# PortBreakoutCapacitive_r3_no_user.net
KiCad netlist of a schematic drawn in EAGLE
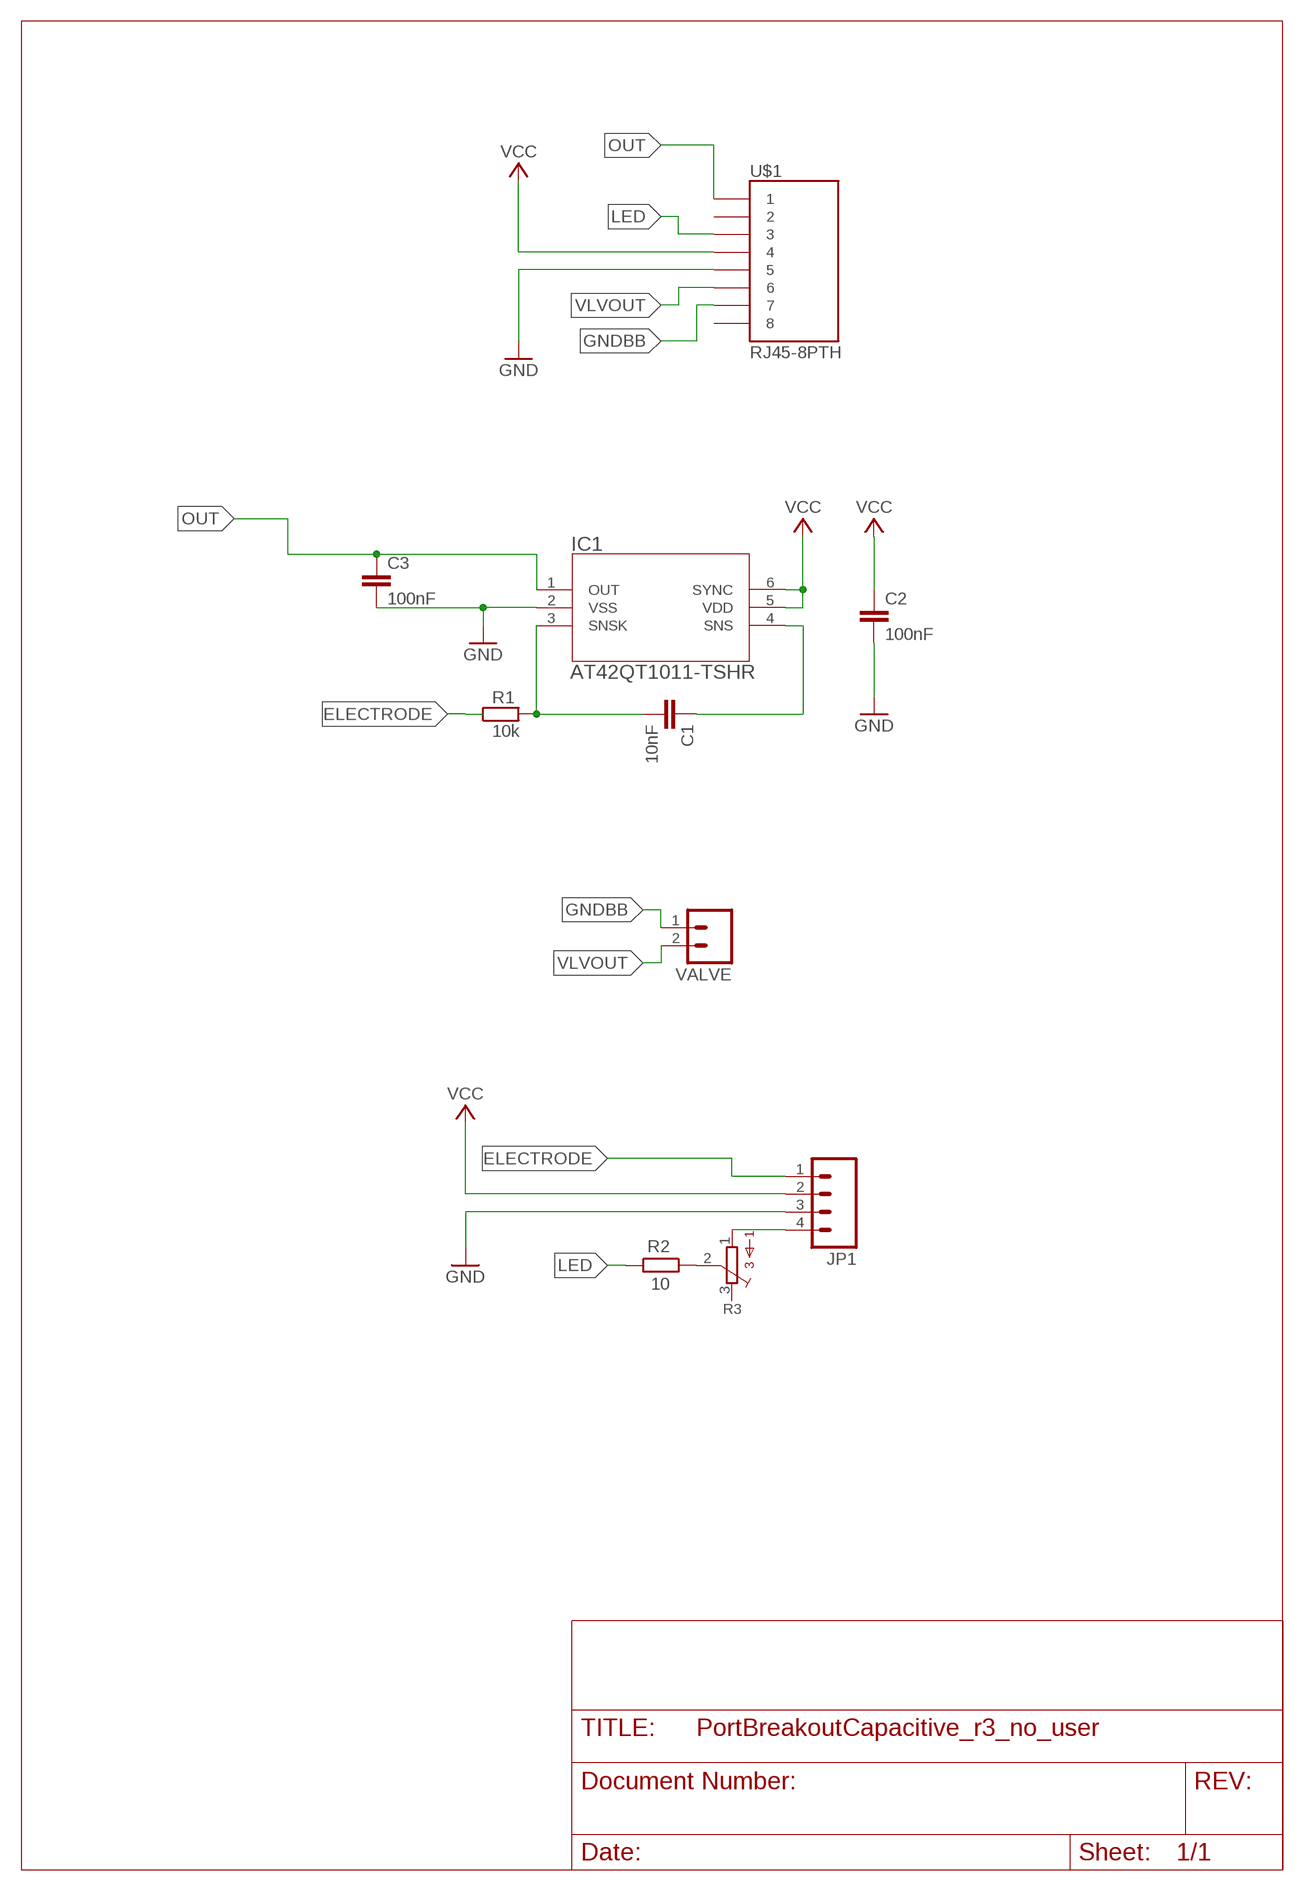
[diagram p0: schematic, sheet 1]

(export (version "E")
  (design (tool "Eeschema 10.0.6"))
  (components
    (comp (ref "C1")
      (value "10nF")
      (footprint "eagle-import:C1206")
      (libsource (lib "eagle-import") (part "C-EUC1206"))
    )
    (comp (ref "C2")
      (value "100nF")
      (footprint "eagle-import:C1206")
      (libsource (lib "eagle-import") (part "C-EUC1206"))
    )
    (comp (ref "C3")
      (value "100nF")
      (footprint "eagle-import:C1206")
      (libsource (lib "eagle-import") (part "C-EUC1206"))
    )
    (comp (ref "IC1")
      (value "AT42QT1011-TSHR")
      (footprint "eagle-import:6ST1_ATM")
      (fields (field (name "MANUFACTURER_PART_NUMBER") "AT42QT1010-TSHR"))
      (libsource (lib "eagle-import") (part "AT42QT1010-TSHR"))
    )
    (comp (ref "JP1")
      (value "CONN_04SCREW")
      (footprint "eagle-import:SCREWTERMINAL-3.5MM-4")
      (libsource (lib "eagle-import") (part "CONN_04SCREW"))
    )
    (comp (ref "R1")
      (value "10k")
      (footprint "eagle-import:R1206")
      (libsource (lib "eagle-import") (part "R-EU_R1206"))
    )
    (comp (ref "R2")
      (value "10")
      (footprint "eagle-import:R1206")
      (libsource (lib "eagle-import") (part "R-EU_R1206"))
    )
    (comp (ref "R3")
      (value "3362R")
      (footprint "eagle-import:3362R")
      (libsource (lib "eagle-import") (part "3362R"))
    )
    (comp (ref "U$1")
      (value "RJ45-8PTH")
      (footprint "eagle-import:RJ45-8")
      (libsource (lib "eagle-import") (part "RJ45-8PTH"))
    )
    (comp (ref "VALVE")
      (value "M023.5MM_LOCK")
      (footprint "eagle-import:SCREWTERMINAL-3.5MM-2_LOCK")
      (libsource (lib "eagle-import") (part "M023.5MM_LOCK"))
    )
  )
  (nets
    (net (code "1") (name "ELECTRODE") (class "Default")
      (node (ref "JP1") (pin "1") (pinfunction "1_1") (pintype "passive"))
      (node (ref "R1") (pin "1") (pinfunction "1_1") (pintype "passive"))
    )
    (net (code "2") (name "GND") (class "Default")
      (node (ref "C2") (pin "2") (pinfunction "2_2") (pintype "passive"))
      (node (ref "C3") (pin "2") (pinfunction "2_2") (pintype "passive"))
      (node (ref "IC1") (pin "2") (pinfunction "VSS_2") (pintype "power_in"))
      (node (ref "JP1") (pin "3") (pinfunction "3_3") (pintype "passive"))
      (node (ref "U$1") (pin "5") (pinfunction "5_5") (pintype "bidirectional"))
    )
    (net (code "3") (name "GNDBB") (class "Default")
      (node (ref "U$1") (pin "7") (pinfunction "7_7") (pintype "bidirectional"))
      (node (ref "VALVE") (pin "1") (pinfunction "1_1") (pintype "passive"))
    )
    (net (code "4") (name "LED") (class "Default")
      (node (ref "R2") (pin "2") (pinfunction "2_2") (pintype "passive"))
      (node (ref "U$1") (pin "3") (pinfunction "3_3") (pintype "bidirectional"))
    )
    (net (code "5") (name "Net-(IC1-SNS)") (class "Default")
      (node (ref "C1") (pin "1") (pinfunction "1_1") (pintype "passive"))
      (node (ref "IC1") (pin "4") (pinfunction "SNS_4") (pintype "bidirectional"))
    )
    (net (code "6") (name "Net-(IC1-SNSK)") (class "Default")
      (node (ref "C1") (pin "2") (pinfunction "2_2") (pintype "passive"))
      (node (ref "IC1") (pin "3") (pinfunction "SNSK_3") (pintype "bidirectional"))
      (node (ref "R1") (pin "2") (pinfunction "2_2") (pintype "passive"))
    )
    (net (code "7") (name "Net-(JP1-Pad4)") (class "Default")
      (node (ref "JP1") (pin "4") (pinfunction "4_4") (pintype "passive"))
      (node (ref "R3") (pin "1") (pinfunction "1_1") (pintype "passive"))
    )
    (net (code "8") (name "Net-(R2-Pad1)") (class "Default")
      (node (ref "R2") (pin "1") (pinfunction "1_1") (pintype "passive"))
      (node (ref "R3") (pin "2") (pinfunction "2_2") (pintype "passive"))
    )
    (net (code "9") (name "OUT") (class "Default")
      (node (ref "C3") (pin "1") (pinfunction "1_1") (pintype "passive"))
      (node (ref "IC1") (pin "1") (pinfunction "OUT_1") (pintype "output"))
      (node (ref "U$1") (pin "1") (pinfunction "1_1") (pintype "bidirectional"))
    )
    (net (code "10") (name "VCC") (class "Default")
      (node (ref "C2") (pin "1") (pinfunction "1_1") (pintype "passive"))
      (node (ref "IC1") (pin "5") (pinfunction "VDD_5") (pintype "power_in"))
      (node (ref "IC1") (pin "6") (pinfunction "SYNC_6") (pintype "input"))
      (node (ref "JP1") (pin "2") (pinfunction "2_2") (pintype "passive"))
      (node (ref "U$1") (pin "4") (pinfunction "4_4") (pintype "bidirectional"))
    )
    (net (code "11") (name "VLVOUT") (class "Default")
      (node (ref "U$1") (pin "6") (pinfunction "6_6") (pintype "bidirectional"))
      (node (ref "VALVE") (pin "2") (pinfunction "2_2") (pintype "passive"))
    )
    (net (code "12") (name "unconnected-(R3-Pad3)") (class "Default")
      (node (ref "R3") (pin "3") (pinfunction "3_3") (pintype "passive"))
    )
    (net (code "13") (name "unconnected-(U$1-Pad2)") (class "Default")
      (node (ref "U$1") (pin "2") (pinfunction "2_2") (pintype "bidirectional"))
    )
    (net (code "14") (name "unconnected-(U$1-Pad8)") (class "Default")
      (node (ref "U$1") (pin "8") (pinfunction "8_8") (pintype "bidirectional"))
    )
  )
)
